# BlancerCar.net
KiCad netlist of a schematic drawn in Altium Designer
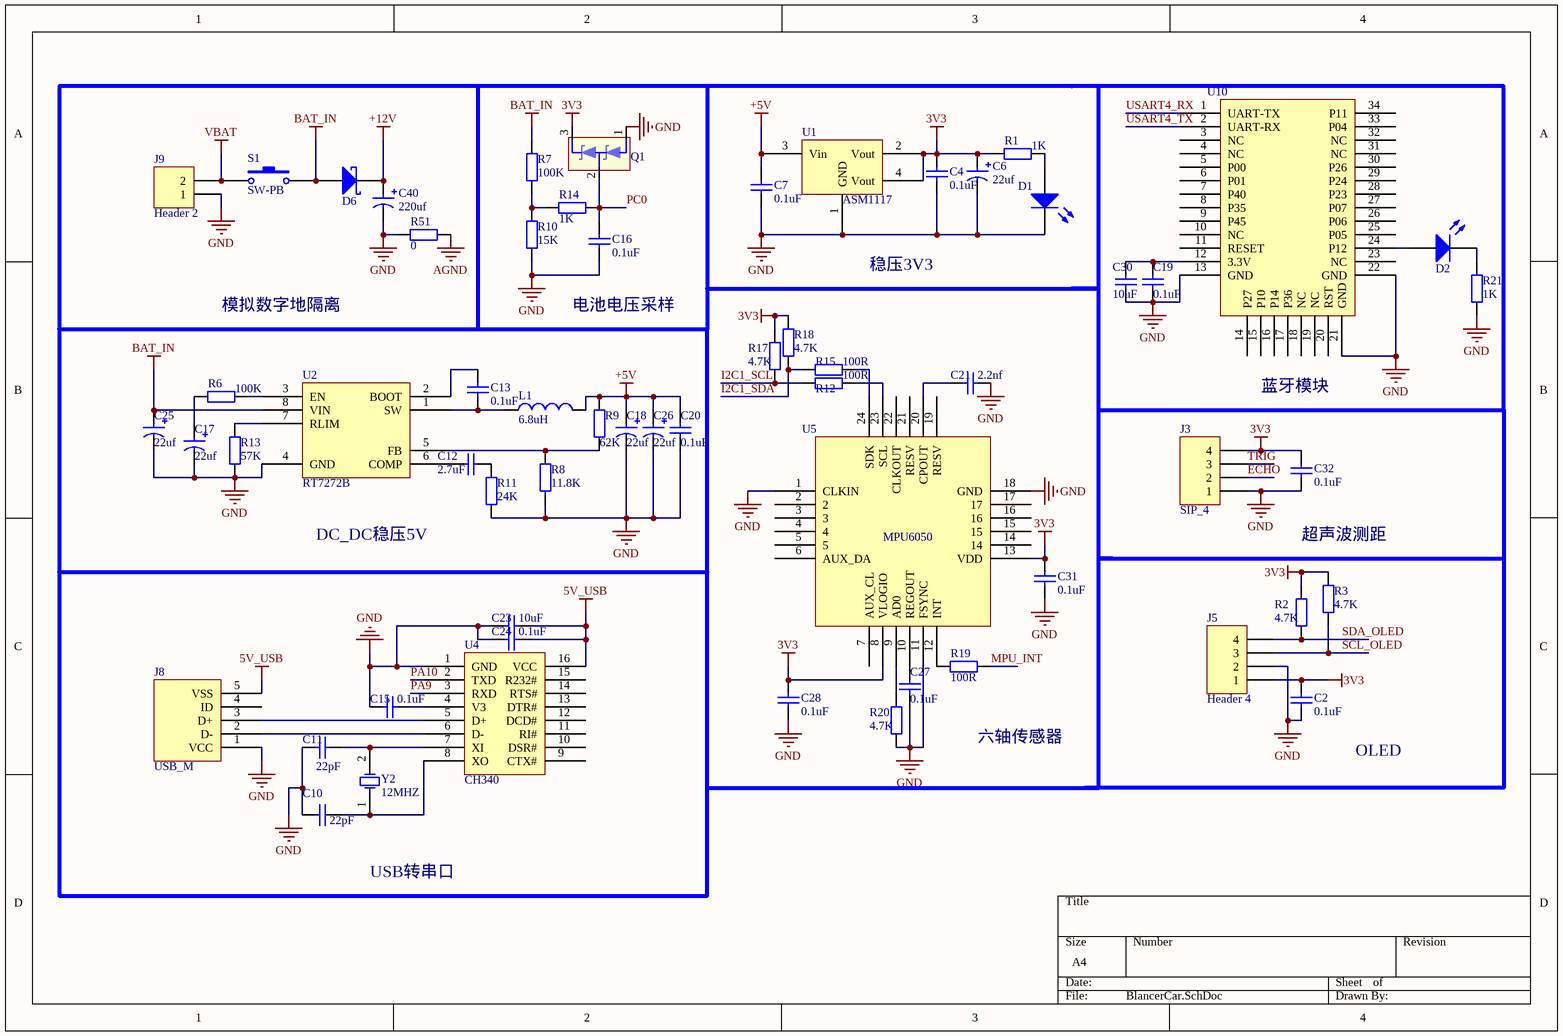
[diagram p0: BlancerCar.SchDoc]

(export (version "E")
  (design (tool "Eeschema 10.0.6"))
  (components
    (comp (ref "C2")
      (value "0.1uF")
      (footprint "0805-1")
      (description "Capacitor")
      (fields (field (name "Comment") "Cap") (field (name "PUBLISHER") "Altium Limited"))
      (libsource (lib "BlancerCar") (part "Cap"))
    )
    (comp (ref "C4")
      (value "0.1uF")
      (footprint "0805-1")
      (description "Capacitor")
      (fields (field (name "Comment") "Cap") (field (name "PUBLISHER") "Altium Limited"))
      (libsource (lib "BlancerCar") (part "Cap"))
    )
    (comp (ref "C6")
      (value "22uf")
      (footprint "钽电容XDH")
      (fields (field (name "Comment") "Cap钽电容"))
      (libsource (lib "BlancerCar") (part "Cap-dan"))
    )
    (comp (ref "C7")
      (value "0.1uF")
      (footprint "0805-1")
      (description "Capacitor")
      (fields (field (name "Comment") "Cap") (field (name "PUBLISHER") "Altium Limited"))
      (libsource (lib "BlancerCar") (part "Cap"))
    )
    (comp (ref "C10")
      (value "22pF")
      (footprint "0805-1")
      (description "Capacitor")
      (fields (field (name "Comment") "Cap") (field (name "PUBLISHER") "Altium Limited"))
      (libsource (lib "BlancerCar") (part "Cap"))
    )
    (comp (ref "C11")
      (value "22pF")
      (footprint "0805-1")
      (description "Capacitor")
      (fields (field (name "Comment") "Cap") (field (name "PUBLISHER") "Altium Limited"))
      (libsource (lib "BlancerCar") (part "Cap"))
    )
    (comp (ref "C12")
      (value "2.7uF")
      (footprint "0805-1")
      (description "Capacitor")
      (fields (field (name "Comment") "Cap") (field (name "PUBLISHER") "Altium Limited"))
      (libsource (lib "BlancerCar") (part "Cap"))
    )
    (comp (ref "C13")
      (value "0.1uF")
      (footprint "0805-1")
      (description "Capacitor")
      (fields (field (name "Comment") "Cap") (field (name "PUBLISHER") "Altium Limited"))
      (libsource (lib "BlancerCar") (part "Cap"))
    )
    (comp (ref "C15")
      (value "0.1uF")
      (footprint "0805-1")
      (description "Capacitor")
      (fields (field (name "Comment") "Cap") (field (name "PUBLISHER") "Altium Limited"))
      (libsource (lib "BlancerCar") (part "Cap"))
    )
    (comp (ref "C16")
      (value "0.1uF")
      (footprint "0805-1")
      (description "Capacitor")
      (fields (field (name "Comment") "Cap") (field (name "PUBLISHER") "Altium Limited"))
      (libsource (lib "BlancerCar") (part "Cap"))
    )
    (comp (ref "C17")
      (value "22uf")
      (footprint "钽电容XDH")
      (fields (field (name "Comment") "Cap钽电容"))
      (libsource (lib "BlancerCar") (part "Cap-dan"))
    )
    (comp (ref "C18")
      (value "22uf")
      (footprint "钽电容XDH")
      (fields (field (name "Comment") "Cap钽电容"))
      (libsource (lib "BlancerCar") (part "Cap-dan"))
    )
    (comp (ref "C19")
      (value "0.1uF")
      (footprint "0805-1")
      (description "Capacitor")
      (fields (field (name "Comment") "Cap") (field (name "PUBLISHER") "Altium Limited"))
      (libsource (lib "BlancerCar") (part "Cap"))
    )
    (comp (ref "C20")
      (value "0.1uF")
      (footprint "0805-1")
      (description "Capacitor")
      (fields (field (name "Comment") "Cap") (field (name "PUBLISHER") "Altium Limited"))
      (libsource (lib "BlancerCar") (part "Cap"))
    )
    (comp (ref "C21")
      (value "2.2nf")
      (footprint "0805-1")
      (description "Capacitor")
      (fields (field (name "Comment") "Cap") (field (name "PUBLISHER") "Altium Limited"))
      (libsource (lib "BlancerCar") (part "Cap"))
    )
    (comp (ref "C23")
      (value "10uF")
      (footprint "0805-1")
      (description "Capacitor")
      (fields (field (name "Comment") "Cap") (field (name "PUBLISHER") "Altium Limited"))
      (libsource (lib "BlancerCar") (part "Cap"))
    )
    (comp (ref "C24")
      (value "0.1uF")
      (footprint "0805-1")
      (description "Capacitor")
      (fields (field (name "Comment") "Cap") (field (name "PUBLISHER") "Altium Limited"))
      (libsource (lib "BlancerCar") (part "Cap"))
    )
    (comp (ref "C25")
      (value "22uf")
      (footprint "钽电容XDH")
      (fields (field (name "Comment") "Cap钽电容"))
      (libsource (lib "BlancerCar") (part "Cap-dan"))
    )
    (comp (ref "C26")
      (value "22uf")
      (footprint "钽电容XDH")
      (fields (field (name "Comment") "Cap钽电容"))
      (libsource (lib "BlancerCar") (part "Cap-dan"))
    )
    (comp (ref "C27")
      (value "0.1uF")
      (footprint "0805-1")
      (description "Capacitor")
      (fields (field (name "Comment") "Cap") (field (name "PUBLISHER") "Altium Limited"))
      (libsource (lib "BlancerCar") (part "Cap"))
    )
    (comp (ref "C28")
      (value "0.1uF")
      (footprint "0805-1")
      (description "Capacitor")
      (fields (field (name "Comment") "Cap") (field (name "PUBLISHER") "Altium Limited"))
      (libsource (lib "BlancerCar") (part "Cap"))
    )
    (comp (ref "C30")
      (value "10uF")
      (footprint "0805-1")
      (description "Capacitor")
      (fields (field (name "Comment") "Cap") (field (name "PUBLISHER") "Altium Limited"))
      (libsource (lib "BlancerCar") (part "Cap"))
    )
    (comp (ref "C31")
      (value "0.1uF")
      (footprint "0805-1")
      (description "Capacitor")
      (fields (field (name "Comment") "Cap") (field (name "PUBLISHER") "Altium Limited"))
      (libsource (lib "BlancerCar") (part "Cap"))
    )
    (comp (ref "C32")
      (value "0.1uF")
      (footprint "0805-1")
      (description "Capacitor")
      (fields (field (name "Comment") "Cap") (field (name "PUBLISHER") "Altium Limited"))
      (libsource (lib "BlancerCar") (part "Cap"))
    )
    (comp (ref "C40")
      (value "220uf")
      (footprint "电容220UF")
      (fields (field (name "Comment") "Cap钽电容"))
      (libsource (lib "BlancerCar") (part "Cap-dan"))
    )
    (comp (ref "D1")
      (value "LED0")
      (footprint "LED_0805")
      (description "发光二极管")
      (fields (field (name "PUBLISHER") "Altium Limited"))
      (libsource (lib "") (part "LED0_1"))
    )
    (comp (ref "D2")
      (value "LED0")
      (footprint "LED_0805")
      (description "发光二极管")
      (fields (field (name "PUBLISHER") "Altium Limited"))
      (libsource (lib "xdhADL") (part "LED0"))
    )
    (comp (ref "D6") (value "肖基特二极管") (footprint "SS54") (libsource (lib "BlancerCar") (part "SS54")))
    (comp (ref "J3")
      (value "SIP_4")
      (footprint "HDR1X4")
      (description "Header, 4-Pin")
      (fields (field (name "PUBLISHER") "Altium Limited"))
      (libsource (lib "BlancerCar") (part "Header 4"))
    )
    (comp (ref "J5")
      (value "Header 4")
      (footprint "HDR1X4")
      (description "Header, 4-Pin")
      (fields (field (name "PUBLISHER") "Altium Limited"))
      (libsource (lib "BlancerCar") (part "Header 4"))
    )
    (comp (ref "J8")
      (value "USB_M")
      (footprint "USB_MICRO")
      (description "MicroUSB接口")
      (libsource (lib "xdhADL") (part "USB_M"))
    )
    (comp (ref "J9")
      (value "Header 2")
      (footprint "T字公头")
      (description "Header, 2-Pin")
      (fields (field (name "PUBLISHER") "Altium Limited"))
      (libsource (lib "BlancerCar") (part "Header 2"))
    )
    (comp (ref "L1")
      (value "6.8uH")
      (footprint "33uh电感")
      (description "Inductor")
      (fields (field (name "PUBLISHER") "Altium Limited"))
      (libsource (lib "BlancerCar") (part "Inductor"))
    )
    (comp (ref "Q1")
      (value "肖基特二极管")
      (footprint "BAT54S(SOT-23-3)")
      (libsource (lib "BlancerCar") (part "BAT54S"))
    )
    (comp (ref "R1")
      (value "1K")
      (footprint "0805-1")
      (description "贴片电阻")
      (fields (field (name "Comment") "Res1") (field (name "PUBLISHER") "Altium Limited"))
      (libsource (lib "") (part "Res1_1"))
    )
    (comp (ref "R2")
      (value "4.7K")
      (footprint "0805-1")
      (description "贴片电阻")
      (fields (field (name "Comment") "Res1") (field (name "PUBLISHER") "Altium Limited"))
      (libsource (lib "xdhADL") (part "Res1"))
    )
    (comp (ref "R3")
      (value "4.7K")
      (footprint "0805-1")
      (description "贴片电阻")
      (fields (field (name "Comment") "Res1") (field (name "PUBLISHER") "Altium Limited"))
      (libsource (lib "xdhADL") (part "Res1"))
    )
    (comp (ref "R6")
      (value "100K")
      (footprint "0805-1")
      (description "贴片电阻")
      (fields (field (name "Comment") "Res1") (field (name "PUBLISHER") "Altium Limited"))
      (libsource (lib "") (part "Res1_1"))
    )
    (comp (ref "R7")
      (value "100K")
      (footprint "0805-1")
      (description "贴片电阻")
      (fields (field (name "Comment") "Res1") (field (name "PUBLISHER") "Altium Limited"))
      (libsource (lib "xdhADL") (part "Res1"))
    )
    (comp (ref "R8")
      (value "11.8K")
      (footprint "0805-1")
      (description "贴片电阻")
      (fields (field (name "Comment") "Res1") (field (name "PUBLISHER") "Altium Limited"))
      (libsource (lib "xdhADL") (part "Res1"))
    )
    (comp (ref "R9")
      (value "62K")
      (footprint "0805-1")
      (description "贴片电阻")
      (fields (field (name "Comment") "Res1") (field (name "PUBLISHER") "Altium Limited"))
      (libsource (lib "xdhADL") (part "Res1"))
    )
    (comp (ref "R10")
      (value "15K")
      (footprint "0805-1")
      (description "贴片电阻")
      (fields (field (name "Comment") "Res1") (field (name "PUBLISHER") "Altium Limited"))
      (libsource (lib "xdhADL") (part "Res1"))
    )
    (comp (ref "R11")
      (value "24K")
      (footprint "0805-1")
      (description "贴片电阻")
      (fields (field (name "Comment") "Res1") (field (name "PUBLISHER") "Altium Limited"))
      (libsource (lib "xdhADL") (part "Res1"))
    )
    (comp (ref "R12")
      (value "100R")
      (footprint "0805-1")
      (description "贴片电阻")
      (fields (field (name "Comment") "Res1") (field (name "PUBLISHER") "Altium Limited"))
      (libsource (lib "") (part "Res1_2"))
    )
    (comp (ref "R13")
      (value "57K")
      (footprint "0805-1")
      (description "贴片电阻")
      (fields (field (name "Comment") "Res1") (field (name "PUBLISHER") "Altium Limited"))
      (libsource (lib "xdhADL") (part "Res1"))
    )
    (comp (ref "R14")
      (value "1K")
      (footprint "0805-1")
      (description "贴片电阻")
      (fields (field (name "Comment") "Res1") (field (name "PUBLISHER") "Altium Limited"))
      (libsource (lib "") (part "Res1_2"))
    )
    (comp (ref "R15")
      (value "100R")
      (footprint "0805-1")
      (description "贴片电阻")
      (fields (field (name "Comment") "Res1") (field (name "PUBLISHER") "Altium Limited"))
      (libsource (lib "") (part "Res1_2"))
    )
    (comp (ref "R17")
      (value "4.7K")
      (footprint "0805-1")
      (description "贴片电阻")
      (fields (field (name "Comment") "Res1") (field (name "PUBLISHER") "Altium Limited"))
      (libsource (lib "xdhADL") (part "Res1"))
    )
    (comp (ref "R18")
      (value "4.7K")
      (footprint "0805-1")
      (description "贴片电阻")
      (fields (field (name "Comment") "Res1") (field (name "PUBLISHER") "Altium Limited"))
      (libsource (lib "xdhADL") (part "Res1"))
    )
    (comp (ref "R19")
      (value "100R")
      (footprint "0805-1")
      (description "贴片电阻")
      (fields (field (name "Comment") "Res1") (field (name "PUBLISHER") "Altium Limited"))
      (libsource (lib "") (part "Res1_2"))
    )
    (comp (ref "R20")
      (value "4.7K")
      (footprint "0805-1")
      (description "贴片电阻")
      (fields (field (name "Comment") "Res1") (field (name "PUBLISHER") "Altium Limited"))
      (libsource (lib "xdhADL") (part "Res1"))
    )
    (comp (ref "R21")
      (value "1K")
      (footprint "0805-1")
      (description "贴片电阻")
      (fields (field (name "Comment") "Res1") (field (name "PUBLISHER") "Altium Limited"))
      (libsource (lib "xdhADL") (part "Res1"))
    )
    (comp (ref "R51")
      (value "0")
      (footprint "0805-1")
      (description "贴片电阻")
      (fields (field (name "Comment") "Res1") (field (name "PUBLISHER") "Altium Limited"))
      (libsource (lib "") (part "Res1_1"))
    )
    (comp (ref "S1")
      (value "SW-PB")
      (footprint "开关 6A")
      (description "Switch")
      (fields (field (name "PUBLISHER") "Altium Limited"))
      (libsource (lib "BlancerCar") (part "SW-PB"))
    )
    (comp (ref "U1") (value "ASM1117") (footprint "ASM1117") (libsource (lib "BlancerCar") (part "ASM1117")))
    (comp (ref "U2")
      (value "RT7272B")
      (footprint "SOIC_8(LC)")
      (description "RT7272B同步降压型DC-DC转换器")
      (libsource (lib "BlancerCar") (part "RT7272B"))
    )
    (comp (ref "U4") (value "CH340") (footprint "SOP16") (libsource (lib "BlancerCar") (part "CH340")))
    (comp (ref "U5") (value "MPU6050") (footprint "MPU6050") (libsource (lib "BlancerCar") (part "MPU6050_")))
    (comp (ref "U10") (value "蓝牙模块") (footprint "LANYA") (libsource (lib "BlancerCar") (part "蓝牙")))
    (comp (ref "Y2")
      (value "12MHZ")
      (footprint "晶振 8M")
      (description "Crystal Oscillator")
      (fields (field (name "PUBLISHER") "Altium Limited"))
      (libsource (lib "BlancerCar") (part "XTAL"))
    )
  )
  (nets
    (net (code "1") (name "+5V") (class "Default")
      (node (ref "C18") (pin "1") (pinfunction "1_1") (pintype "passive"))
      (node (ref "C20") (pin "1") (pinfunction "1_1") (pintype "passive"))
      (node (ref "C26") (pin "1") (pinfunction "1_1") (pintype "passive"))
      (node (ref "C7") (pin "2") (pinfunction "2_2") (pintype "passive"))
      (node (ref "L1") (pin "2") (pinfunction "2_2") (pintype "passive"))
      (node (ref "R9") (pin "2") (pinfunction "2_2") (pintype "passive"))
      (node (ref "U1") (pin "3") (pinfunction "Vin_3") (pintype "passive"))
    )
    (net (code "2") (name "+12V") (class "Default")
      (node (ref "C40") (pin "1") (pinfunction "1_1") (pintype "passive"))
      (node (ref "D6") (pin "2") (pinfunction "K_2") (pintype "passive"))
    )
    (net (code "3") (name "/ECHO") (class "Default")
      (node (ref "J3") (pin "2") (pinfunction "2_2") (pintype "passive"))
    )
    (net (code "4") (name "/I2C1_SCL") (class "Default")
      (node (ref "R12") (pin "2") (pinfunction "2_2") (pintype "passive"))
      (node (ref "R17") (pin "1") (pinfunction "1_1") (pintype "passive"))
    )
    (net (code "5") (name "/I2C1_SDA") (class "Default")
      (node (ref "R15") (pin "2") (pinfunction "2_2") (pintype "passive"))
      (node (ref "R18") (pin "1") (pinfunction "1_1") (pintype "passive"))
    )
    (net (code "6") (name "/MPU_INT") (class "Default")
      (node (ref "R19") (pin "1") (pinfunction "1_1") (pintype "passive"))
    )
    (net (code "7") (name "/PA9") (class "Default")
      (node (ref "U4") (pin "3") (pinfunction "RXD_3") (pintype "passive"))
    )
    (net (code "8") (name "/PA10") (class "Default")
      (node (ref "U4") (pin "2") (pinfunction "TXD_2") (pintype "passive"))
    )
    (net (code "9") (name "/PC0") (class "Default")
      (node (ref "C16") (pin "2") (pinfunction "2_2") (pintype "passive"))
      (node (ref "Q1") (pin "2") (pinfunction "2_2") (pintype "passive"))
      (node (ref "R14") (pin "1") (pinfunction "1_1") (pintype "passive"))
    )
    (net (code "10") (name "/SCL_OLED") (class "Default")
      (node (ref "J5") (pin "3") (pinfunction "3_3") (pintype "passive"))
      (node (ref "R3") (pin "1") (pinfunction "1_1") (pintype "passive"))
    )
    (net (code "11") (name "/SDA_OLED") (class "Default")
      (node (ref "J5") (pin "4") (pinfunction "4_4") (pintype "passive"))
      (node (ref "R2") (pin "1") (pinfunction "1_1") (pintype "passive"))
    )
    (net (code "12") (name "/TRIG") (class "Default")
      (node (ref "J3") (pin "3") (pinfunction "3_3") (pintype "passive"))
    )
    (net (code "13") (name "/USART4_RX") (class "Default")
      (node (ref "U10") (pin "1") (pinfunction "UART-TX_1") (pintype "passive"))
    )
    (net (code "14") (name "/USART4_TX") (class "Default")
      (node (ref "U10") (pin "2") (pinfunction "UART-RX_2") (pintype "passive"))
    )
    (net (code "15") (name "3V3") (class "Default")
      (node (ref "C2") (pin "2") (pinfunction "2_2") (pintype "passive"))
      (node (ref "C28") (pin "2") (pinfunction "2_2") (pintype "passive"))
      (node (ref "C31") (pin "2") (pinfunction "2_2") (pintype "passive"))
      (node (ref "C32") (pin "2") (pinfunction "2_2") (pintype "passive"))
      (node (ref "C4") (pin "2") (pinfunction "2_2") (pintype "passive"))
      (node (ref "C6") (pin "1") (pinfunction "1_1") (pintype "passive"))
      (node (ref "J3") (pin "4") (pinfunction "4_4") (pintype "passive"))
      (node (ref "J5") (pin "1") (pinfunction "1_1") (pintype "passive"))
      (node (ref "Q1") (pin "3") (pinfunction "3_3") (pintype "passive"))
      (node (ref "R1") (pin "1") (pinfunction "1_1") (pintype "passive"))
      (node (ref "R17") (pin "2") (pinfunction "2_2") (pintype "passive"))
      (node (ref "R18") (pin "2") (pinfunction "2_2") (pintype "passive"))
      (node (ref "R2") (pin "2") (pinfunction "2_2") (pintype "passive"))
      (node (ref "R3") (pin "2") (pinfunction "2_2") (pintype "passive"))
      (node (ref "U1") (pin "2") (pinfunction "Vout_2") (pintype "passive"))
      (node (ref "U1") (pin "4") (pinfunction "Vout_4") (pintype "passive"))
      (node (ref "U5") (pin "13") (pinfunction "VDD_13") (pintype "passive"))
      (node (ref "U5") (pin "8") (pinfunction "VLOGIO_8") (pintype "passive"))
    )
    (net (code "16") (name "5V_USB") (class "Default")
      (node (ref "C23") (pin "2") (pinfunction "2_2") (pintype "passive"))
      (node (ref "C24") (pin "2") (pinfunction "2_2") (pintype "passive"))
      (node (ref "J8") (pin "5") (pinfunction "VSS_5") (pintype "passive"))
      (node (ref "U4") (pin "16") (pinfunction "VCC_16") (pintype "passive"))
    )
    (net (code "17") (name "AGND") (class "Default")
      (node (ref "R51") (pin "2") (pinfunction "2_2") (pintype "passive"))
    )
    (net (code "18") (name "BAT_IN") (class "Default")
      (node (ref "C25") (pin "1") (pinfunction "1_1") (pintype "passive"))
      (node (ref "D6") (pin "1") (pinfunction "A_1") (pintype "passive"))
      (node (ref "R7") (pin "2") (pinfunction "2_2") (pintype "passive"))
      (node (ref "S1") (pin "2") (pinfunction "2_2") (pintype "passive"))
      (node (ref "U2") (pin "8") (pinfunction "VIN_8") (pintype "passive"))
    )
    (net (code "19") (name "GND") (class "Default")
      (node (ref "C10") (pin "2") (pinfunction "2_2") (pintype "passive"))
      (node (ref "C11") (pin "2") (pinfunction "2_2") (pintype "passive"))
      (node (ref "C15") (pin "1") (pinfunction "1_1") (pintype "passive"))
      (node (ref "C16") (pin "1") (pinfunction "1_1") (pintype "passive"))
      (node (ref "C17") (pin "2") (pinfunction "2_2") (pintype "passive"))
      (node (ref "C18") (pin "2") (pinfunction "2_2") (pintype "passive"))
      (node (ref "C19") (pin "1") (pinfunction "1_1") (pintype "passive"))
      (node (ref "C2") (pin "1") (pinfunction "1_1") (pintype "passive"))
      (node (ref "C20") (pin "2") (pinfunction "2_2") (pintype "passive"))
      (node (ref "C21") (pin "2") (pinfunction "2_2") (pintype "passive"))
      (node (ref "C23") (pin "1") (pinfunction "1_1") (pintype "passive"))
      (node (ref "C24") (pin "1") (pinfunction "1_1") (pintype "passive"))
      (node (ref "C25") (pin "2") (pinfunction "2_2") (pintype "passive"))
      (node (ref "C26") (pin "2") (pinfunction "2_2") (pintype "passive"))
      (node (ref "C27") (pin "1") (pinfunction "1_1") (pintype "passive"))
      (node (ref "C28") (pin "1") (pinfunction "1_1") (pintype "passive"))
      (node (ref "C30") (pin "1") (pinfunction "1_1") (pintype "passive"))
      (node (ref "C31") (pin "1") (pinfunction "1_1") (pintype "passive"))
      (node (ref "C32") (pin "1") (pinfunction "1_1") (pintype "passive"))
      (node (ref "C4") (pin "1") (pinfunction "1_1") (pintype "passive"))
      (node (ref "C40") (pin "2") (pinfunction "2_2") (pintype "passive"))
      (node (ref "C6") (pin "2") (pinfunction "2_2") (pintype "passive"))
      (node (ref "C7") (pin "1") (pinfunction "1_1") (pintype "passive"))
      (node (ref "D1") (pin "2") (pinfunction "K_2") (pintype "passive"))
      (node (ref "J3") (pin "1") (pinfunction "1_1") (pintype "passive"))
      (node (ref "J5") (pin "2") (pinfunction "2_2") (pintype "passive"))
      (node (ref "J8") (pin "1") (pinfunction "VCC_1") (pintype "passive"))
      (node (ref "J9") (pin "1") (pinfunction "1_1") (pintype "passive"))
      (node (ref "Q1") (pin "1") (pinfunction "1_1") (pintype "passive"))
      (node (ref "R10") (pin "1") (pinfunction "1_1") (pintype "passive"))
      (node (ref "R11") (pin "1") (pinfunction "1_1") (pintype "passive"))
      (node (ref "R13") (pin "1") (pinfunction "1_1") (pintype "passive"))
      (node (ref "R20") (pin "1") (pinfunction "1_1") (pintype "passive"))
      (node (ref "R21") (pin "1") (pinfunction "1_1") (pintype "passive"))
      (node (ref "R51") (pin "1") (pinfunction "1_1") (pintype "passive"))
      (node (ref "R8") (pin "1") (pinfunction "1_1") (pintype "passive"))
      (node (ref "U1") (pin "1") (pinfunction "GND_1") (pintype "passive"))
      (node (ref "U10") (pin "13") (pinfunction "GND_13") (pintype "passive"))
      (node (ref "U10") (pin "21") (pinfunction "GND_21") (pintype "passive"))
      (node (ref "U10") (pin "22") (pinfunction "GND_22") (pintype "passive"))
      (node (ref "U2") (pin "4") (pinfunction "GND_4") (pintype "passive"))
      (node (ref "U4") (pin "1") (pinfunction "GND_1") (pintype "passive"))
      (node (ref "U5") (pin "1") (pinfunction "CLKIN_1") (pintype "passive"))
      (node (ref "U5") (pin "11") (pinfunction "FSYNC_11") (pintype "passive"))
      (node (ref "U5") (pin "18") (pinfunction "GND_18") (pintype "passive"))
    )
    (net (code "20") (name "Net-(C12-Pad2)") (class "Default")
      (node (ref "C12") (pin "2") (pinfunction "2_2") (pintype "passive"))
      (node (ref "R11") (pin "2") (pinfunction "2_2") (pintype "passive"))
    )
    (net (code "21") (name "Net-(C17-Pad1)") (class "Default")
      (node (ref "C17") (pin "1") (pinfunction "1_1") (pintype "passive"))
      (node (ref "R6") (pin "1") (pinfunction "1_1") (pintype "passive"))
    )
    (net (code "22") (name "Net-(D1-A)") (class "Default")
      (node (ref "D1") (pin "1") (pinfunction "A_1") (pintype "passive"))
      (node (ref "R1") (pin "2") (pinfunction "2_2") (pintype "passive"))
    )
    (net (code "23") (name "Net-(D2-A)") (class "Default")
      (node (ref "D2") (pin "1") (pinfunction "A_1") (pintype "passive"))
      (node (ref "U10") (pin "24") (pinfunction "P12_24") (pintype "passive"))
    )
    (net (code "24") (name "Net-(D2-K)") (class "Default")
      (node (ref "D2") (pin "2") (pinfunction "K_2") (pintype "passive"))
      (node (ref "R21") (pin "2") (pinfunction "2_2") (pintype "passive"))
    )
    (net (code "25") (name "Net-(J8-D+)") (class "Default")
      (node (ref "J8") (pin "3") (pinfunction "D+_3") (pintype "passive"))
      (node (ref "U4") (pin "5") (pinfunction "D+_5") (pintype "passive"))
    )
    (net (code "26") (name "Net-(J8-D-)") (class "Default")
      (node (ref "J8") (pin "2") (pinfunction "D-_2") (pintype "passive"))
      (node (ref "U4") (pin "6") (pinfunction "D-_6") (pintype "passive"))
    )
    (net (code "27") (name "Net-(R10-Pad2)") (class "Default")
      (node (ref "R10") (pin "2") (pinfunction "2_2") (pintype "passive"))
      (node (ref "R14") (pin "2") (pinfunction "2_2") (pintype "passive"))
      (node (ref "R7") (pin "1") (pinfunction "1_1") (pintype "passive"))
    )
    (net (code "28") (name "Net-(U2-BOOT)") (class "Default")
      (node (ref "C13") (pin "2") (pinfunction "2_2") (pintype "passive"))
      (node (ref "U2") (pin "2") (pinfunction "BOOT_2") (pintype "passive"))
    )
    (net (code "29") (name "Net-(U2-COMP)") (class "Default")
      (node (ref "C12") (pin "1") (pinfunction "1_1") (pintype "passive"))
      (node (ref "U2") (pin "6") (pinfunction "COMP_6") (pintype "passive"))
    )
    (net (code "30") (name "Net-(U2-EN)") (class "Default")
      (node (ref "R6") (pin "2") (pinfunction "2_2") (pintype "passive"))
      (node (ref "U2") (pin "3") (pinfunction "EN_3") (pintype "passive"))
    )
    (net (code "31") (name "Net-(U2-FB)") (class "Default")
      (node (ref "R8") (pin "2") (pinfunction "2_2") (pintype "passive"))
      (node (ref "R9") (pin "1") (pinfunction "1_1") (pintype "passive"))
      (node (ref "U2") (pin "5") (pinfunction "FB_5") (pintype "passive"))
    )
    (net (code "32") (name "Net-(U2-RLIM)") (class "Default")
      (node (ref "R13") (pin "2") (pinfunction "2_2") (pintype "passive"))
      (node (ref "U2") (pin "7") (pinfunction "RLIM_7") (pintype "passive"))
    )
    (net (code "33") (name "Net-(U2-SW)") (class "Default")
      (node (ref "C13") (pin "1") (pinfunction "1_1") (pintype "passive"))
      (node (ref "L1") (pin "1") (pinfunction "1_1") (pintype "passive"))
      (node (ref "U2") (pin "1") (pinfunction "SW_1") (pintype "passive"))
    )
    (net (code "34") (name "Net-(U4-V3)") (class "Default")
      (node (ref "C15") (pin "2") (pinfunction "2_2") (pintype "passive"))
      (node (ref "U4") (pin "4") (pinfunction "V3_4") (pintype "passive"))
    )
    (net (code "35") (name "Net-(U4-XI)") (class "Default")
      (node (ref "C11") (pin "1") (pinfunction "1_1") (pintype "passive"))
      (node (ref "U4") (pin "7") (pinfunction "XI_7") (pintype "passive"))
      (node (ref "Y2") (pin "2") (pinfunction "OSC2_2") (pintype "passive"))
    )
    (net (code "36") (name "Net-(U4-XO)") (class "Default")
      (node (ref "C10") (pin "1") (pinfunction "1_1") (pintype "passive"))
      (node (ref "U4") (pin "8") (pinfunction "XO_8") (pintype "passive"))
      (node (ref "Y2") (pin "1") (pinfunction "OSC1_1") (pintype "passive"))
    )
    (net (code "37") (name "Net-(U5-AD0)") (class "Default")
      (node (ref "R20") (pin "2") (pinfunction "2_2") (pintype "passive"))
      (node (ref "U5") (pin "9") (pinfunction "AD0_9") (pintype "passive"))
    )
    (net (code "38") (name "Net-(U5-CPOUT)") (class "Default")
      (node (ref "C21") (pin "1") (pinfunction "1_1") (pintype "passive"))
      (node (ref "U5") (pin "20") (pinfunction "CPOUT_20") (pintype "passive"))
    )
    (net (code "39") (name "Net-(U5-INT)") (class "Default")
      (node (ref "R19") (pin "2") (pinfunction "2_2") (pintype "passive"))
      (node (ref "U5") (pin "12") (pinfunction "INT_12") (pintype "passive"))
    )
    (net (code "40") (name "Net-(U5-REGOUT)") (class "Default")
      (node (ref "C27") (pin "2") (pinfunction "2_2") (pintype "passive"))
      (node (ref "U5") (pin "10") (pinfunction "REGOUT_10") (pintype "passive"))
    )
    (net (code "41") (name "Net-(U5-SCL)") (class "Default")
      (node (ref "R12") (pin "1") (pinfunction "1_1") (pintype "passive"))
      (node (ref "U5") (pin "23") (pinfunction "SCL_23") (pintype "passive"))
    )
    (net (code "42") (name "Net-(U5-SDK)") (class "Default")
      (node (ref "R15") (pin "1") (pinfunction "1_1") (pintype "passive"))
      (node (ref "U5") (pin "24") (pinfunction "SDK_24") (pintype "passive"))
    )
    (net (code "43") (name "Net-(U10-3.3V)") (class "Default")
      (node (ref "C19") (pin "2") (pinfunction "2_2") (pintype "passive"))
      (node (ref "C30") (pin "2") (pinfunction "2_2") (pintype "passive"))
      (node (ref "U10") (pin "12") (pinfunction "3.3V_12") (pintype "passive"))
    )
    (net (code "44") (name "VBAT") (class "Default")
      (node (ref "J9") (pin "2") (pinfunction "2_2") (pintype "passive"))
      (node (ref "S1") (pin "1") (pinfunction "1_1") (pintype "passive"))
    )
    (net (code "45") (name "unconnected-(J8-ID-Pad4)") (class "Default")
      (node (ref "J8") (pin "4") (pinfunction "ID_4") (pintype "passive"))
    )
    (net (code "46") (name "unconnected-(U4-CTX#-Pad9)") (class "Default")
      (node (ref "U4") (pin "9") (pinfunction "CTX#_9") (pintype "passive"))
    )
    (net (code "47") (name "unconnected-(U4-DCD#-Pad12)") (class "Default")
      (node (ref "U4") (pin "12") (pinfunction "DCD#_12") (pintype "passive"))
    )
    (net (code "48") (name "unconnected-(U4-DSR#-Pad10)") (class "Default")
      (node (ref "U4") (pin "10") (pinfunction "DSR#_10") (pintype "passive"))
    )
    (net (code "49") (name "unconnected-(U4-DTR#-Pad13)") (class "Default")
      (node (ref "U4") (pin "13") (pinfunction "DTR#_13") (pintype "passive"))
    )
    (net (code "50") (name "unconnected-(U4-R232#-Pad15)") (class "Default")
      (node (ref "U4") (pin "15") (pinfunction "R232#_15") (pintype "passive"))
    )
    (net (code "51") (name "unconnected-(U4-RI#-Pad11)") (class "Default")
      (node (ref "U4") (pin "11") (pinfunction "RI#_11") (pintype "passive"))
    )
    (net (code "52") (name "unconnected-(U4-RTS#-Pad14)") (class "Default")
      (node (ref "U4") (pin "14") (pinfunction "RTS#_14") (pintype "passive"))
    )
    (net (code "53") (name "unconnected-(U5-AUX_CL-Pad7)") (class "Default")
      (node (ref "U5") (pin "7") (pinfunction "AUX_CL_7") (pintype "passive"))
    )
    (net (code "54") (name "unconnected-(U5-AUX_DA-Pad6)") (class "Default")
      (node (ref "U5") (pin "6") (pinfunction "AUX_DA_6") (pintype "passive"))
    )
    (net (code "55") (name "unconnected-(U5-CLKOUT-Pad22)") (class "Default")
      (node (ref "U5") (pin "22") (pinfunction "CLKOUT_22") (pintype "passive"))
    )
    (net (code "56") (name "unconnected-(U5-Pad2)") (class "Default")
      (node (ref "U5") (pin "2") (pinfunction "2_2") (pintype "passive"))
    )
    (net (code "57") (name "unconnected-(U5-Pad3)") (class "Default")
      (node (ref "U5") (pin "3") (pinfunction "3_3") (pintype "passive"))
    )
    (net (code "58") (name "unconnected-(U5-Pad4)") (class "Default")
      (node (ref "U5") (pin "4") (pinfunction "4_4") (pintype "passive"))
    )
    (net (code "59") (name "unconnected-(U5-Pad5)") (class "Default")
      (node (ref "U5") (pin "5") (pinfunction "5_5") (pintype "passive"))
    )
    (net (code "60") (name "unconnected-(U5-Pad14)") (class "Default")
      (node (ref "U5") (pin "14") (pinfunction "14_14") (pintype "passive"))
    )
    (net (code "61") (name "unconnected-(U5-Pad15)") (class "Default")
      (node (ref "U5") (pin "15") (pinfunction "15_15") (pintype "passive"))
    )
    (net (code "62") (name "unconnected-(U5-Pad16)") (class "Default")
      (node (ref "U5") (pin "16") (pinfunction "16_16") (pintype "passive"))
    )
    (net (code "63") (name "unconnected-(U5-Pad17)") (class "Default")
      (node (ref "U5") (pin "17") (pinfunction "17_17") (pintype "passive"))
    )
    (net (code "64") (name "unconnected-(U5-RESV-Pad19)") (class "Default")
      (node (ref "U5") (pin "19") (pinfunction "RESV_19") (pintype "passive"))
    )
    (net (code "65") (name "unconnected-(U5-RESV-Pad21)") (class "Default")
      (node (ref "U5") (pin "21") (pinfunction "RESV_21") (pintype "passive"))
    )
    (net (code "66") (name "unconnected-(U10-NC-Pad3)") (class "Default")
      (node (ref "U10") (pin "3") (pinfunction "NC_3") (pintype "passive"))
    )
    (net (code "67") (name "unconnected-(U10-NC-Pad4)") (class "Default")
      (node (ref "U10") (pin "4") (pinfunction "NC_4") (pintype "passive"))
    )
    (net (code "68") (name "unconnected-(U10-NC-Pad10)") (class "Default")
      (node (ref "U10") (pin "10") (pinfunction "NC_10") (pintype "passive"))
    )
    (net (code "69") (name "unconnected-(U10-NC-Pad18)") (class "Default")
      (node (ref "U10") (pin "18") (pinfunction "NC_18") (pintype "passive"))
    )
    (net (code "70") (name "unconnected-(U10-NC-Pad19)") (class "Default")
      (node (ref "U10") (pin "19") (pinfunction "NC_19") (pintype "passive"))
    )
    (net (code "71") (name "unconnected-(U10-NC-Pad23)") (class "Default")
      (node (ref "U10") (pin "23") (pinfunction "NC_23") (pintype "passive"))
    )
    (net (code "72") (name "unconnected-(U10-NC-Pad31)") (class "Default")
      (node (ref "U10") (pin "31") (pinfunction "NC_31") (pintype "passive"))
    )
    (net (code "73") (name "unconnected-(U10-NC-Pad32)") (class "Default")
      (node (ref "U10") (pin "32") (pinfunction "NC_32") (pintype "passive"))
    )
    (net (code "74") (name "unconnected-(U10-P00-Pad5)") (class "Default")
      (node (ref "U10") (pin "5") (pinfunction "P00_5") (pintype "passive"))
    )
    (net (code "75") (name "unconnected-(U10-P01-Pad6)") (class "Default")
      (node (ref "U10") (pin "6") (pinfunction "P01_6") (pintype "passive"))
    )
    (net (code "76") (name "unconnected-(U10-P04-Pad33)") (class "Default")
      (node (ref "U10") (pin "33") (pinfunction "P04_33") (pintype "passive"))
    )
    (net (code "77") (name "unconnected-(U10-P05-Pad25)") (class "Default")
      (node (ref "U10") (pin "25") (pinfunction "P05_25") (pintype "passive"))
    )
    (net (code "78") (name "unconnected-(U10-P06-Pad26)") (class "Default")
      (node (ref "U10") (pin "26") (pinfunction "P06_26") (pintype "passive"))
    )
    (net (code "79") (name "unconnected-(U10-P07-Pad27)") (class "Default")
      (node (ref "U10") (pin "27") (pinfunction "P07_27") (pintype "passive"))
    )
    (net (code "80") (name "unconnected-(U10-P10-Pad15)") (class "Default")
      (node (ref "U10") (pin "15") (pinfunction "P10_15") (pintype "passive"))
    )
    (net (code "81") (name "unconnected-(U10-P11-Pad34)") (class "Default")
      (node (ref "U10") (pin "34") (pinfunction "P11_34") (pintype "passive"))
    )
    (net (code "82") (name "unconnected-(U10-P14-Pad16)") (class "Default")
      (node (ref "U10") (pin "16") (pinfunction "P14_16") (pintype "passive"))
    )
    (net (code "83") (name "unconnected-(U10-P23-Pad28)") (class "Default")
      (node (ref "U10") (pin "28") (pinfunction "P23_28") (pintype "passive"))
    )
    (net (code "84") (name "unconnected-(U10-P24-Pad29)") (class "Default")
      (node (ref "U10") (pin "29") (pinfunction "P24_29") (pintype "passive"))
    )
    (net (code "85") (name "unconnected-(U10-P26-Pad30)") (class "Default")
      (node (ref "U10") (pin "30") (pinfunction "P26_30") (pintype "passive"))
    )
    (net (code "86") (name "unconnected-(U10-P27-Pad14)") (class "Default")
      (node (ref "U10") (pin "14") (pinfunction "P27_14") (pintype "passive"))
    )
    (net (code "87") (name "unconnected-(U10-P35-Pad8)") (class "Default")
      (node (ref "U10") (pin "8") (pinfunction "P35_8") (pintype "passive"))
    )
    (net (code "88") (name "unconnected-(U10-P36-Pad17)") (class "Default")
      (node (ref "U10") (pin "17") (pinfunction "P36_17") (pintype "passive"))
    )
    (net (code "89") (name "unconnected-(U10-P40-Pad7)") (class "Default")
      (node (ref "U10") (pin "7") (pinfunction "P40_7") (pintype "passive"))
    )
    (net (code "90") (name "unconnected-(U10-P45-Pad9)") (class "Default")
      (node (ref "U10") (pin "9") (pinfunction "P45_9") (pintype "passive"))
    )
    (net (code "91") (name "unconnected-(U10-RESET-Pad11)") (class "Default")
      (node (ref "U10") (pin "11") (pinfunction "RESET_11") (pintype "passive"))
    )
    (net (code "92") (name "unconnected-(U10-RST-Pad20)") (class "Default")
      (node (ref "U10") (pin "20") (pinfunction "RST_20") (pintype "passive"))
    )
  )
)
